# SLT3-PAY-1Q2T_P5.net
KiCad netlist of a schematic drawn in Altium Designer
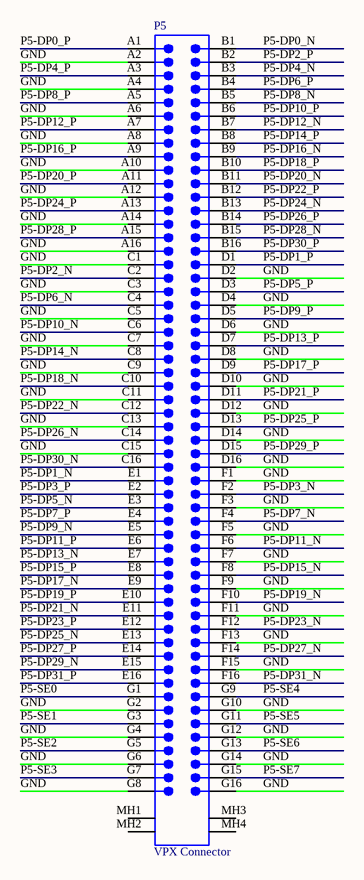
[diagram p0: SLT3-PAY-1Q2T_P5.SchDoc]

(export (version "E")
  (design (tool "Eeschema 10.0.6"))
  (components
    (comp (ref "P5")
      (value "VPX Connector")
      (footprint "BTB1-8-4H112M")
      (description "Ruggedized Board-to-Board Connector, Right Angle, 7-Row, Pitch 1.8mm, 112-Position")
      (fields (field (name "MANUFACTURER") "TE") (field (name "MANUFACTURER PART NUMBER") "2102771-1"))
      (libsource (lib "SVPX") (part "2102771-1"))
    )
  )
  (nets
    (net (code "1") (name "/GND") (class "Default")
      (node (ref "P5") (pin "A10") (pinfunction "A10_A10") (pintype "passive"))
      (node (ref "P5") (pin "A12") (pinfunction "A12_A12") (pintype "passive"))
      (node (ref "P5") (pin "A14") (pinfunction "A14_A14") (pintype "passive"))
      (node (ref "P5") (pin "A16") (pinfunction "A16_A16") (pintype "passive"))
      (node (ref "P5") (pin "A2") (pinfunction "A2_A2") (pintype "passive"))
      (node (ref "P5") (pin "A4") (pinfunction "A4_A4") (pintype "passive"))
      (node (ref "P5") (pin "A6") (pinfunction "A6_A6") (pintype "passive"))
      (node (ref "P5") (pin "A8") (pinfunction "A8_A8") (pintype "passive"))
      (node (ref "P5") (pin "C1") (pinfunction "C1_C1") (pintype "passive"))
      (node (ref "P5") (pin "C11") (pinfunction "C11_C11") (pintype "passive"))
      (node (ref "P5") (pin "C13") (pinfunction "C13_C13") (pintype "passive"))
      (node (ref "P5") (pin "C15") (pinfunction "C15_C15") (pintype "passive"))
      (node (ref "P5") (pin "C3") (pinfunction "C3_C3") (pintype "passive"))
      (node (ref "P5") (pin "C5") (pinfunction "C5_C5") (pintype "passive"))
      (node (ref "P5") (pin "C7") (pinfunction "C7_C7") (pintype "passive"))
      (node (ref "P5") (pin "C9") (pinfunction "C9_C9") (pintype "passive"))
      (node (ref "P5") (pin "D10") (pinfunction "D10_D10") (pintype "passive"))
      (node (ref "P5") (pin "D12") (pinfunction "D12_D12") (pintype "passive"))
      (node (ref "P5") (pin "D14") (pinfunction "D14_D14") (pintype "passive"))
      (node (ref "P5") (pin "D16") (pinfunction "D16_D16") (pintype "passive"))
      (node (ref "P5") (pin "D2") (pinfunction "D2_D2") (pintype "passive"))
      (node (ref "P5") (pin "D4") (pinfunction "D4_D4") (pintype "passive"))
      (node (ref "P5") (pin "D6") (pinfunction "D6_D6") (pintype "passive"))
      (node (ref "P5") (pin "D8") (pinfunction "D8_D8") (pintype "passive"))
      (node (ref "P5") (pin "F1") (pinfunction "F1_F1") (pintype "passive"))
      (node (ref "P5") (pin "F11") (pinfunction "F11_F11") (pintype "passive"))
      (node (ref "P5") (pin "F13") (pinfunction "F13_F13") (pintype "passive"))
      (node (ref "P5") (pin "F15") (pinfunction "F15_F15") (pintype "passive"))
      (node (ref "P5") (pin "F3") (pinfunction "F3_F3") (pintype "passive"))
      (node (ref "P5") (pin "F5") (pinfunction "F5_F5") (pintype "passive"))
      (node (ref "P5") (pin "F7") (pinfunction "F7_F7") (pintype "passive"))
      (node (ref "P5") (pin "F9") (pinfunction "F9_F9") (pintype "passive"))
      (node (ref "P5") (pin "G10") (pinfunction "G10_G10") (pintype "passive"))
      (node (ref "P5") (pin "G12") (pinfunction "G12_G12") (pintype "passive"))
      (node (ref "P5") (pin "G14") (pinfunction "G14_G14") (pintype "passive"))
      (node (ref "P5") (pin "G16") (pinfunction "G16_G16") (pintype "passive"))
      (node (ref "P5") (pin "G2") (pinfunction "G2_G2") (pintype "passive"))
      (node (ref "P5") (pin "G4") (pinfunction "G4_G4") (pintype "passive"))
      (node (ref "P5") (pin "G6") (pinfunction "G6_G6") (pintype "passive"))
      (node (ref "P5") (pin "G8") (pinfunction "G8_G8") (pintype "passive"))
    )
    (net (code "2") (name "/P5-DP0_N") (class "Default")
      (node (ref "P5") (pin "B1") (pinfunction "B1_B1") (pintype "passive"))
    )
    (net (code "3") (name "/P5-DP0_P") (class "Default")
      (node (ref "P5") (pin "A1") (pinfunction "A1_A1") (pintype "passive"))
    )
    (net (code "4") (name "/P5-DP1_N") (class "Default")
      (node (ref "P5") (pin "E1") (pinfunction "E1_E1") (pintype "passive"))
    )
    (net (code "5") (name "/P5-DP1_P") (class "Default")
      (node (ref "P5") (pin "D1") (pinfunction "D1_D1") (pintype "passive"))
    )
    (net (code "6") (name "/P5-DP2_N") (class "Default")
      (node (ref "P5") (pin "C2") (pinfunction "C2_C2") (pintype "passive"))
    )
    (net (code "7") (name "/P5-DP2_P") (class "Default")
      (node (ref "P5") (pin "B2") (pinfunction "B2_B2") (pintype "passive"))
    )
    (net (code "8") (name "/P5-DP3_N") (class "Default")
      (node (ref "P5") (pin "F2") (pinfunction "F2_F2") (pintype "passive"))
    )
    (net (code "9") (name "/P5-DP3_P") (class "Default")
      (node (ref "P5") (pin "E2") (pinfunction "E2_E2") (pintype "passive"))
    )
    (net (code "10") (name "/P5-DP4_N") (class "Default")
      (node (ref "P5") (pin "B3") (pinfunction "B3_B3") (pintype "passive"))
    )
    (net (code "11") (name "/P5-DP4_P") (class "Default")
      (node (ref "P5") (pin "A3") (pinfunction "A3_A3") (pintype "passive"))
    )
    (net (code "12") (name "/P5-DP5_N") (class "Default")
      (node (ref "P5") (pin "E3") (pinfunction "E3_E3") (pintype "passive"))
    )
    (net (code "13") (name "/P5-DP5_P") (class "Default")
      (node (ref "P5") (pin "D3") (pinfunction "D3_D3") (pintype "passive"))
    )
    (net (code "14") (name "/P5-DP6_N") (class "Default")
      (node (ref "P5") (pin "C4") (pinfunction "C4_C4") (pintype "passive"))
    )
    (net (code "15") (name "/P5-DP6_P") (class "Default")
      (node (ref "P5") (pin "B4") (pinfunction "B4_B4") (pintype "passive"))
    )
    (net (code "16") (name "/P5-DP7_N") (class "Default")
      (node (ref "P5") (pin "F4") (pinfunction "F4_F4") (pintype "passive"))
    )
    (net (code "17") (name "/P5-DP7_P") (class "Default")
      (node (ref "P5") (pin "E4") (pinfunction "E4_E4") (pintype "passive"))
    )
    (net (code "18") (name "/P5-DP8_N") (class "Default")
      (node (ref "P5") (pin "B5") (pinfunction "B5_B5") (pintype "passive"))
    )
    (net (code "19") (name "/P5-DP8_P") (class "Default")
      (node (ref "P5") (pin "A5") (pinfunction "A5_A5") (pintype "passive"))
    )
    (net (code "20") (name "/P5-DP9_N") (class "Default")
      (node (ref "P5") (pin "E5") (pinfunction "E5_E5") (pintype "passive"))
    )
    (net (code "21") (name "/P5-DP9_P") (class "Default")
      (node (ref "P5") (pin "D5") (pinfunction "D5_D5") (pintype "passive"))
    )
    (net (code "22") (name "/P5-DP10_N") (class "Default")
      (node (ref "P5") (pin "C6") (pinfunction "C6_C6") (pintype "passive"))
    )
    (net (code "23") (name "/P5-DP10_P") (class "Default")
      (node (ref "P5") (pin "B6") (pinfunction "B6_B6") (pintype "passive"))
    )
    (net (code "24") (name "/P5-DP11_N") (class "Default")
      (node (ref "P5") (pin "F6") (pinfunction "F6_F6") (pintype "passive"))
    )
    (net (code "25") (name "/P5-DP11_P") (class "Default")
      (node (ref "P5") (pin "E6") (pinfunction "E6_E6") (pintype "passive"))
    )
    (net (code "26") (name "/P5-DP12_N") (class "Default")
      (node (ref "P5") (pin "B7") (pinfunction "B7_B7") (pintype "passive"))
    )
    (net (code "27") (name "/P5-DP12_P") (class "Default")
      (node (ref "P5") (pin "A7") (pinfunction "A7_A7") (pintype "passive"))
    )
    (net (code "28") (name "/P5-DP13_N") (class "Default")
      (node (ref "P5") (pin "E7") (pinfunction "E7_E7") (pintype "passive"))
    )
    (net (code "29") (name "/P5-DP13_P") (class "Default")
      (node (ref "P5") (pin "D7") (pinfunction "D7_D7") (pintype "passive"))
    )
    (net (code "30") (name "/P5-DP14_N") (class "Default")
      (node (ref "P5") (pin "C8") (pinfunction "C8_C8") (pintype "passive"))
    )
    (net (code "31") (name "/P5-DP14_P") (class "Default")
      (node (ref "P5") (pin "B8") (pinfunction "B8_B8") (pintype "passive"))
    )
    (net (code "32") (name "/P5-DP15_N") (class "Default")
      (node (ref "P5") (pin "F8") (pinfunction "F8_F8") (pintype "passive"))
    )
    (net (code "33") (name "/P5-DP15_P") (class "Default")
      (node (ref "P5") (pin "E8") (pinfunction "E8_E8") (pintype "passive"))
    )
    (net (code "34") (name "/P5-DP16_N") (class "Default")
      (node (ref "P5") (pin "B9") (pinfunction "B9_B9") (pintype "passive"))
    )
    (net (code "35") (name "/P5-DP16_P") (class "Default")
      (node (ref "P5") (pin "A9") (pinfunction "A9_A9") (pintype "passive"))
    )
    (net (code "36") (name "/P5-DP17_N") (class "Default")
      (node (ref "P5") (pin "E9") (pinfunction "E9_E9") (pintype "passive"))
    )
    (net (code "37") (name "/P5-DP17_P") (class "Default")
      (node (ref "P5") (pin "D9") (pinfunction "D9_D9") (pintype "passive"))
    )
    (net (code "38") (name "/P5-DP18_N") (class "Default")
      (node (ref "P5") (pin "C10") (pinfunction "C10_C10") (pintype "passive"))
    )
    (net (code "39") (name "/P5-DP18_P") (class "Default")
      (node (ref "P5") (pin "B10") (pinfunction "B10_B10") (pintype "passive"))
    )
    (net (code "40") (name "/P5-DP19_N") (class "Default")
      (node (ref "P5") (pin "F10") (pinfunction "F10_F10") (pintype "passive"))
    )
    (net (code "41") (name "/P5-DP19_P") (class "Default")
      (node (ref "P5") (pin "E10") (pinfunction "E10_E10") (pintype "passive"))
    )
    (net (code "42") (name "/P5-DP20_N") (class "Default")
      (node (ref "P5") (pin "B11") (pinfunction "B11_B11") (pintype "passive"))
    )
    (net (code "43") (name "/P5-DP20_P") (class "Default")
      (node (ref "P5") (pin "A11") (pinfunction "A11_A11") (pintype "passive"))
    )
    (net (code "44") (name "/P5-DP21_N") (class "Default")
      (node (ref "P5") (pin "E11") (pinfunction "E11_E11") (pintype "passive"))
    )
    (net (code "45") (name "/P5-DP21_P") (class "Default")
      (node (ref "P5") (pin "D11") (pinfunction "D11_D11") (pintype "passive"))
    )
    (net (code "46") (name "/P5-DP22_N") (class "Default")
      (node (ref "P5") (pin "C12") (pinfunction "C12_C12") (pintype "passive"))
    )
    (net (code "47") (name "/P5-DP22_P") (class "Default")
      (node (ref "P5") (pin "B12") (pinfunction "B12_B12") (pintype "passive"))
    )
    (net (code "48") (name "/P5-DP23_N") (class "Default")
      (node (ref "P5") (pin "F12") (pinfunction "F12_F12") (pintype "passive"))
    )
    (net (code "49") (name "/P5-DP23_P") (class "Default")
      (node (ref "P5") (pin "E12") (pinfunction "E12_E12") (pintype "passive"))
    )
    (net (code "50") (name "/P5-DP24_N") (class "Default")
      (node (ref "P5") (pin "B13") (pinfunction "B13_B13") (pintype "passive"))
    )
    (net (code "51") (name "/P5-DP24_P") (class "Default")
      (node (ref "P5") (pin "A13") (pinfunction "A13_A13") (pintype "passive"))
    )
    (net (code "52") (name "/P5-DP25_N") (class "Default")
      (node (ref "P5") (pin "E13") (pinfunction "E13_E13") (pintype "passive"))
    )
    (net (code "53") (name "/P5-DP25_P") (class "Default")
      (node (ref "P5") (pin "D13") (pinfunction "D13_D13") (pintype "passive"))
    )
    (net (code "54") (name "/P5-DP26_N") (class "Default")
      (node (ref "P5") (pin "C14") (pinfunction "C14_C14") (pintype "passive"))
    )
    (net (code "55") (name "/P5-DP26_P") (class "Default")
      (node (ref "P5") (pin "B14") (pinfunction "B14_B14") (pintype "passive"))
    )
    (net (code "56") (name "/P5-DP27_N") (class "Default")
      (node (ref "P5") (pin "F14") (pinfunction "F14_F14") (pintype "passive"))
    )
    (net (code "57") (name "/P5-DP27_P") (class "Default")
      (node (ref "P5") (pin "E14") (pinfunction "E14_E14") (pintype "passive"))
    )
    (net (code "58") (name "/P5-DP28_N") (class "Default")
      (node (ref "P5") (pin "B15") (pinfunction "B15_B15") (pintype "passive"))
    )
    (net (code "59") (name "/P5-DP28_P") (class "Default")
      (node (ref "P5") (pin "A15") (pinfunction "A15_A15") (pintype "passive"))
    )
    (net (code "60") (name "/P5-DP29_N") (class "Default")
      (node (ref "P5") (pin "E15") (pinfunction "E15_E15") (pintype "passive"))
    )
    (net (code "61") (name "/P5-DP29_P") (class "Default")
      (node (ref "P5") (pin "D15") (pinfunction "D15_D15") (pintype "passive"))
    )
    (net (code "62") (name "/P5-DP30_N") (class "Default")
      (node (ref "P5") (pin "C16") (pinfunction "C16_C16") (pintype "passive"))
    )
    (net (code "63") (name "/P5-DP30_P") (class "Default")
      (node (ref "P5") (pin "B16") (pinfunction "B16_B16") (pintype "passive"))
    )
    (net (code "64") (name "/P5-DP31_N") (class "Default")
      (node (ref "P5") (pin "F16") (pinfunction "F16_F16") (pintype "passive"))
    )
    (net (code "65") (name "/P5-DP31_P") (class "Default")
      (node (ref "P5") (pin "E16") (pinfunction "E16_E16") (pintype "passive"))
    )
    (net (code "66") (name "/P5-SE0") (class "Default")
      (node (ref "P5") (pin "G1") (pinfunction "G1_G1") (pintype "passive"))
    )
    (net (code "67") (name "/P5-SE1") (class "Default")
      (node (ref "P5") (pin "G3") (pinfunction "G3_G3") (pintype "passive"))
    )
    (net (code "68") (name "/P5-SE2") (class "Default")
      (node (ref "P5") (pin "G5") (pinfunction "G5_G5") (pintype "passive"))
    )
    (net (code "69") (name "/P5-SE3") (class "Default")
      (node (ref "P5") (pin "G7") (pinfunction "G7_G7") (pintype "passive"))
    )
    (net (code "70") (name "/P5-SE4") (class "Default")
      (node (ref "P5") (pin "G9") (pinfunction "G9_G9") (pintype "passive"))
    )
    (net (code "71") (name "/P5-SE5") (class "Default")
      (node (ref "P5") (pin "G11") (pinfunction "G11_G11") (pintype "passive"))
    )
    (net (code "72") (name "/P5-SE6") (class "Default")
      (node (ref "P5") (pin "G13") (pinfunction "G13_G13") (pintype "passive"))
    )
    (net (code "73") (name "/P5-SE7") (class "Default")
      (node (ref "P5") (pin "G15") (pinfunction "G15_G15") (pintype "passive"))
    )
    (net (code "74") (name "unconnected-(P5-PadMH1)") (class "Default")
      (node (ref "P5") (pin "MH1") (pinfunction "MH1_MH1") (pintype "passive"))
    )
    (net (code "75") (name "unconnected-(P5-PadMH2)") (class "Default")
      (node (ref "P5") (pin "MH2") (pinfunction "MH2_MH2") (pintype "passive"))
    )
    (net (code "76") (name "unconnected-(P5-PadMH3)") (class "Default")
      (node (ref "P5") (pin "MH3") (pinfunction "MH3_MH3") (pintype "passive"))
    )
    (net (code "77") (name "unconnected-(P5-PadMH4)") (class "Default")
      (node (ref "P5") (pin "MH4") (pinfunction "MH4_MH4") (pintype "passive"))
    )
  )
)
